# Apollo_2.net
KiCad netlist of a schematic drawn in Altium Designer
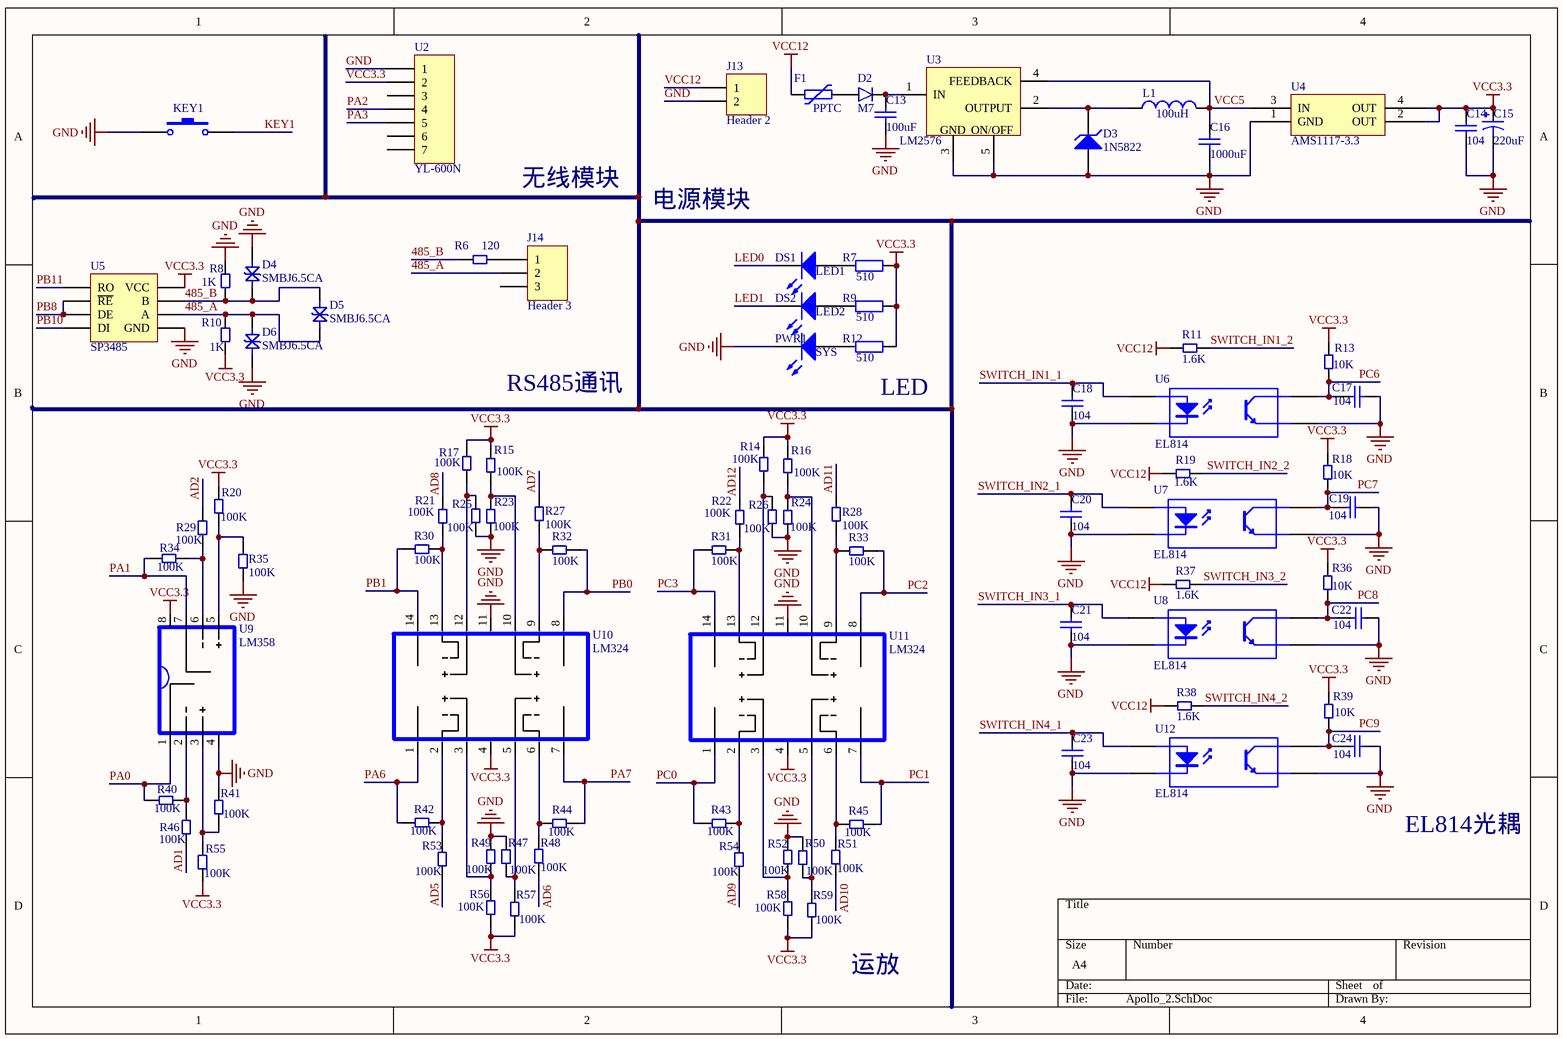
[diagram p0: Apollo_2.SchDoc]

(export (version "E")
  (design (tool "Eeschema 10.0.6"))
  (components
    (comp (ref "C13")
      (value "100uF")
      (footprint "cap3.3-8 - duplicate")
      (description "Capacitor")
      (fields (field (name "PUBLISHER") "Altium Limited"))
      (libsource (lib "Miscellaneous Devices") (part "Cap"))
    )
    (comp (ref "C14")
      (value "104")
      (footprint "0805")
      (description "Capacitor")
      (fields (field (name "Comment") "Cap") (field (name "PUBLISHER") "Altium Limited"))
      (libsource (lib "Miscellaneous Devices") (part "Cap"))
    )
    (comp (ref "C15")
      (value "220uF")
      (footprint "Apollo:C15")
      (description "Polarized Capacitor (Radial)")
      (fields (field (name "Comment") "Cap Pol1") (field (name "PUBLISHER") "Altium Limited"))
      (libsource (lib "Miscellaneous Devices") (part "Cap Pol1"))
    )
    (comp (ref "C16")
      (value "1000uF")
      (footprint "C16")
      (description "Capacitor")
      (fields (field (name "PUBLISHER") "Altium Limited"))
      (libsource (lib "Miscellaneous Devices") (part "Cap"))
    )
    (comp (ref "C17")
      (value "104")
      (footprint "0805C")
      (description "Capacitor")
      (fields (field (name "PUBLISHER") "Altium Limited"))
      (libsource (lib "Miscellaneous Devices") (part "Cap"))
    )
    (comp (ref "C18")
      (value "104")
      (footprint "0805C")
      (description "Capacitor")
      (fields (field (name "PUBLISHER") "Altium Limited"))
      (libsource (lib "Miscellaneous Devices") (part "Cap"))
    )
    (comp (ref "C19")
      (value "104")
      (footprint "0805C")
      (description "Capacitor")
      (fields (field (name "PUBLISHER") "Altium Limited"))
      (libsource (lib "Miscellaneous Devices") (part "Cap"))
    )
    (comp (ref "C20")
      (value "104")
      (footprint "0805C")
      (description "Capacitor")
      (fields (field (name "PUBLISHER") "Altium Limited"))
      (libsource (lib "Miscellaneous Devices") (part "Cap"))
    )
    (comp (ref "C21")
      (value "104")
      (footprint "0805C")
      (description "Capacitor")
      (fields (field (name "PUBLISHER") "Altium Limited"))
      (libsource (lib "Miscellaneous Devices") (part "Cap"))
    )
    (comp (ref "C22")
      (value "104")
      (footprint "0805C")
      (description "Capacitor")
      (fields (field (name "PUBLISHER") "Altium Limited"))
      (libsource (lib "Miscellaneous Devices") (part "Cap"))
    )
    (comp (ref "C23")
      (value "104")
      (footprint "0805C")
      (description "Capacitor")
      (fields (field (name "PUBLISHER") "Altium Limited"))
      (libsource (lib "Miscellaneous Devices") (part "Cap"))
    )
    (comp (ref "C24")
      (value "104")
      (footprint "0805C")
      (description "Capacitor")
      (fields (field (name "PUBLISHER") "Altium Limited"))
      (libsource (lib "Miscellaneous Devices") (part "Cap"))
    )
    (comp (ref "D2") (value "M7") (footprint "SMA (DO-214AC)") (libsource (lib "基本元件") (part "M7")))
    (comp (ref "D3")
      (value "1N5822")
      (footprint "smb do214aa")
      (description "Zener Diode")
      (fields (field (name "PUBLISHER") "Altium Limited"))
      (libsource (lib "Miscellaneous Devices") (part "D Zener"))
    )
    (comp (ref "D4") (value "SMBJ6.5CA") (footprint "smb do214aa") (libsource (lib "基本") (part "SMBJ6.5CA")))
    (comp (ref "D5") (value "SMBJ6.5CA") (footprint "smb do214aa") (libsource (lib "基本") (part "SMBJ6.5CA")))
    (comp (ref "D6") (value "SMBJ6.5CA") (footprint "smb do214aa") (libsource (lib "基本") (part "SMBJ6.5CA")))
    (comp (ref "DS1")
      (value "LED1")
      (footprint "0805-D")
      (description "Typical INFRARED GaAs LED")
      (fields (field (name "PUBLISHER") "Altium Limited"))
      (libsource (lib "Miscellaneous Devices") (part "LED0"))
    )
    (comp (ref "DS2")
      (value "LED2")
      (footprint "0805-D")
      (description "Typical INFRARED GaAs LED")
      (fields (field (name "PUBLISHER") "Altium Limited"))
      (libsource (lib "Miscellaneous Devices") (part "LED0"))
    )
    (comp (ref "F1") (value "PPTC") (footprint "1206") (libsource (lib "基本") (part "PPTC")))
    (comp (ref "J13")
      (value "Header 2")
      (footprint "2EDG 2-3.80")
      (description "Header, 2-Pin")
      (fields (field (name "PUBLISHER") "Altium Limited"))
      (libsource (lib "Miscellaneous Connectors") (part "Header 2"))
    )
    (comp (ref "J14")
      (value "Header 3")
      (footprint "HDR1X3")
      (description "Header, 3-Pin")
      (fields (field (name "PUBLISHER") "Altium Limited"))
      (libsource (lib "Miscellaneous Connectors") (part "Header 3"))
    )
    (comp (ref "KEY1")
      (value "SW-PB")
      (footprint "SWITCH")
      (description "Switch")
      (fields (field (name "PUBLISHER") "Altium Limited"))
      (libsource (lib "Miscellaneous Devices") (part "SW-PB"))
    )
    (comp (ref "L1")
      (value "100uH")
      (footprint "l1212")
      (description "Inductor")
      (fields (field (name "PUBLISHER") "Altium Limited"))
      (libsource (lib "Miscellaneous Devices") (part "Inductor"))
    )
    (comp (ref "PWR1")
      (value "SYS")
      (footprint "0805-D")
      (description "Typical INFRARED GaAs LED")
      (fields (field (name "PUBLISHER") "Altium Limited"))
      (libsource (lib "Miscellaneous Devices") (part "LED0"))
    )
    (comp (ref "R6") (value "120") (footprint "0805") (libsource (lib "基本") (part "Res")))
    (comp (ref "R7")
      (value "510")
      (footprint "0805")
      (description "Resistor")
      (fields (field (name "PUBLISHER") "Altium Limited"))
      (libsource (lib "Miscellaneous Devices") (part "Res2"))
    )
    (comp (ref "R8") (value "1K") (footprint "0805") (libsource (lib "基本") (part "Res")))
    (comp (ref "R9")
      (value "510")
      (footprint "0805")
      (description "Resistor")
      (fields (field (name "PUBLISHER") "Altium Limited"))
      (libsource (lib "Miscellaneous Devices") (part "Res2"))
    )
    (comp (ref "R10") (value "1K") (footprint "0805") (libsource (lib "基本") (part "Res")))
    (comp (ref "R11") (value "1.6K") (footprint "0805") (libsource (lib "基本") (part "Res")))
    (comp (ref "R12")
      (value "510")
      (footprint "0805")
      (description "Resistor")
      (fields (field (name "PUBLISHER") "Altium Limited"))
      (libsource (lib "Miscellaneous Devices") (part "Res2"))
    )
    (comp (ref "R13") (value "10K") (footprint "0805") (libsource (lib "基本") (part "Res")))
    (comp (ref "R14") (value "100K") (footprint "0805") (libsource (lib "基本") (part "Res")))
    (comp (ref "R15") (value "100K") (footprint "0805") (libsource (lib "基本") (part "Res")))
    (comp (ref "R16") (value "100K") (footprint "0805") (libsource (lib "基本") (part "Res")))
    (comp (ref "R17") (value "100K") (footprint "0805") (libsource (lib "基本") (part "Res")))
    (comp (ref "R18") (value "10K") (footprint "0805") (libsource (lib "基本") (part "Res")))
    (comp (ref "R19") (value "1.6K") (footprint "0805") (libsource (lib "基本") (part "Res")))
    (comp (ref "R20") (value "100K") (footprint "0805") (libsource (lib "基本") (part "Res")))
    (comp (ref "R21") (value "100K") (footprint "0805") (libsource (lib "基本") (part "Res")))
    (comp (ref "R22") (value "100K") (footprint "0805") (libsource (lib "基本") (part "Res")))
    (comp (ref "R23") (value "100K") (footprint "0805") (libsource (lib "基本") (part "Res")))
    (comp (ref "R24") (value "100K") (footprint "0805") (libsource (lib "基本") (part "Res")))
    (comp (ref "R25") (value "100K") (footprint "0805") (libsource (lib "基本") (part "Res")))
    (comp (ref "R26") (value "100K") (footprint "0805") (libsource (lib "基本") (part "Res")))
    (comp (ref "R27") (value "100K") (footprint "0805") (libsource (lib "基本") (part "Res")))
    (comp (ref "R28") (value "100K") (footprint "0805") (libsource (lib "基本") (part "Res")))
    (comp (ref "R29") (value "100K") (footprint "0805") (libsource (lib "基本") (part "Res")))
    (comp (ref "R30") (value "100K") (footprint "0805") (libsource (lib "基本") (part "Res")))
    (comp (ref "R31") (value "100K") (footprint "0805") (libsource (lib "基本") (part "Res")))
    (comp (ref "R32") (value "100K") (footprint "0805") (libsource (lib "基本") (part "Res")))
    (comp (ref "R33") (value "100K") (footprint "0805") (libsource (lib "基本") (part "Res")))
    (comp (ref "R34") (value "100K") (footprint "0805") (libsource (lib "基本") (part "Res")))
    (comp (ref "R35") (value "100K") (footprint "0805") (libsource (lib "基本") (part "Res")))
    (comp (ref "R36") (value "10K") (footprint "0805") (libsource (lib "基本") (part "Res")))
    (comp (ref "R37") (value "1.6K") (footprint "0805") (libsource (lib "基本") (part "Res")))
    (comp (ref "R38") (value "1.6K") (footprint "0805") (libsource (lib "基本") (part "Res")))
    (comp (ref "R39") (value "10K") (footprint "0805") (libsource (lib "基本") (part "Res")))
    (comp (ref "R40") (value "100K") (footprint "0805") (libsource (lib "基本") (part "Res")))
    (comp (ref "R41") (value "100K") (footprint "0805") (libsource (lib "基本") (part "Res")))
    (comp (ref "R42") (value "100K") (footprint "0805") (libsource (lib "基本") (part "Res")))
    (comp (ref "R43") (value "100K") (footprint "0805") (libsource (lib "基本") (part "Res")))
    (comp (ref "R44") (value "100K") (footprint "0805") (libsource (lib "基本") (part "Res")))
    (comp (ref "R45") (value "100K") (footprint "0805") (libsource (lib "基本") (part "Res")))
    (comp (ref "R46") (value "100K") (footprint "0805") (libsource (lib "基本") (part "Res")))
    (comp (ref "R47") (value "100K") (footprint "0805") (libsource (lib "基本") (part "Res")))
    (comp (ref "R48") (value "100K") (footprint "0805") (libsource (lib "基本") (part "Res")))
    (comp (ref "R49") (value "100K") (footprint "0805") (libsource (lib "基本") (part "Res")))
    (comp (ref "R50") (value "100K") (footprint "0805") (libsource (lib "基本") (part "Res")))
    (comp (ref "R51") (value "100K") (footprint "0805") (libsource (lib "基本") (part "Res")))
    (comp (ref "R52") (value "100K") (footprint "0805") (libsource (lib "基本") (part "Res")))
    (comp (ref "R53") (value "100K") (footprint "0805") (libsource (lib "基本") (part "Res")))
    (comp (ref "R54") (value "100K") (footprint "0805") (libsource (lib "基本") (part "Res")))
    (comp (ref "R55") (value "100K") (footprint "0805") (libsource (lib "基本") (part "Res")))
    (comp (ref "R56") (value "100K") (footprint "0805") (libsource (lib "基本") (part "Res")))
    (comp (ref "R57") (value "100K") (footprint "0805") (libsource (lib "基本") (part "Res")))
    (comp (ref "R58") (value "100K") (footprint "0805") (libsource (lib "基本") (part "Res")))
    (comp (ref "R59") (value "100K") (footprint "0805") (libsource (lib "基本") (part "Res")))
    (comp (ref "U2")
      (value "YL-600N")
      (footprint "HDR1X7")
      (description "Header, 7-Pin")
      (fields (field (name "PUBLISHER") "Altium Limited"))
      (libsource (lib "Miscellaneous Connectors") (part "Header 7"))
    )
    (comp (ref "U3") (value "LM2576") (footprint "TO-263-5") (libsource (lib "STM32") (part "LM2576")))
    (comp (ref "U4")
      (value "AMS1117-3.3")
      (footprint "AMS1117-3.3")
      (libsource (lib "AMS1117-3.3") (part "AMS1117-3.3"))
    )
    (comp (ref "U5") (value "SP3485") (footprint "sop8") (libsource (lib "常用数字芯片") (part "SP3485")))
    (comp (ref "U6") (value "EL814") (footprint "SOP4") (libsource (lib "*") (part "TLP281")))
    (comp (ref "U7") (value "EL814") (footprint "SOP4") (libsource (lib "*") (part "TLP281")))
    (comp (ref "U8") (value "EL814") (footprint "SOP4") (libsource (lib "*") (part "TLP281")))
    (comp (ref "U9") (value "LM358") (footprint "sop8") (libsource (lib "Apollo") (part "LM358")))
    (comp (ref "U10") (value "LM324") (footprint "SOP-14") (libsource (lib "STM32") (part "LM324N")))
    (comp (ref "U11") (value "LM324") (footprint "SOP-14") (libsource (lib "STM32") (part "LM324N")))
    (comp (ref "U12") (value "EL814") (footprint "SOP4") (libsource (lib "*") (part "TLP281")))
  )
  (nets
    (net (code "1") (name "/485_A") (class "Default")
      (node (ref "D5") (pin "2") (pinfunction "2_2") (pintype "passive"))
      (node (ref "D6") (pin "1") (pinfunction "1_1") (pintype "passive"))
      (node (ref "J14") (pin "2") (pinfunction "2_2") (pintype "passive"))
      (node (ref "R10") (pin "2") (pinfunction "2_2") (pintype "passive"))
      (node (ref "U5") (pin "6") (pinfunction "A_6") (pintype "passive"))
    )
    (net (code "2") (name "/485_B") (class "Default")
      (node (ref "D4") (pin "2") (pinfunction "2_2") (pintype "passive"))
      (node (ref "D5") (pin "1") (pinfunction "1_1") (pintype "passive"))
      (node (ref "R6") (pin "2") (pinfunction "2_2") (pintype "passive"))
      (node (ref "R8") (pin "1") (pinfunction "1_1") (pintype "passive"))
      (node (ref "U5") (pin "7") (pinfunction "B_7") (pintype "passive"))
    )
    (net (code "3") (name "/AD1") (class "Default")
      (node (ref "R46") (pin "1") (pinfunction "1_1") (pintype "passive"))
    )
    (net (code "4") (name "/AD2") (class "Default")
      (node (ref "R29") (pin "2") (pinfunction "2_2") (pintype "passive"))
    )
    (net (code "5") (name "/AD5") (class "Default")
      (node (ref "R53") (pin "1") (pinfunction "1_1") (pintype "passive"))
    )
    (net (code "6") (name "/AD6") (class "Default")
      (node (ref "R48") (pin "1") (pinfunction "1_1") (pintype "passive"))
    )
    (net (code "7") (name "/AD7") (class "Default")
      (node (ref "R27") (pin "1") (pinfunction "1_1") (pintype "passive"))
    )
    (net (code "8") (name "/AD8") (class "Default")
      (node (ref "R21") (pin "1") (pinfunction "1_1") (pintype "passive"))
    )
    (net (code "9") (name "/AD9") (class "Default")
      (node (ref "R54") (pin "1") (pinfunction "1_1") (pintype "passive"))
    )
    (net (code "10") (name "/AD10") (class "Default")
      (node (ref "R51") (pin "1") (pinfunction "1_1") (pintype "passive"))
    )
    (net (code "11") (name "/AD11") (class "Default")
      (node (ref "R28") (pin "1") (pinfunction "1_1") (pintype "passive"))
    )
    (net (code "12") (name "/AD12") (class "Default")
      (node (ref "R22") (pin "1") (pinfunction "1_1") (pintype "passive"))
    )
    (net (code "14") (name "/KEY1") (class "Default")
      (node (ref "KEY1") (pin "2") (pinfunction "2_2") (pintype "passive"))
    )
    (net (code "16") (name "/LED0") (class "Default")
      (node (ref "DS1") (pin "2") (pinfunction "K_2") (pintype "passive"))
    )
    (net (code "17") (name "/LED1") (class "Default")
      (node (ref "DS2") (pin "2") (pinfunction "K_2") (pintype "passive"))
    )
    (net (code "18") (name "/PA0") (class "Default")
      (node (ref "R40") (pin "2") (pinfunction "2_2") (pintype "passive"))
      (node (ref "U9") (pin "1") (pintype "passive"))
    )
    (net (code "19") (name "/PA1") (class "Default")
      (node (ref "R34") (pin "2") (pinfunction "2_2") (pintype "passive"))
      (node (ref "U9") (pin "7") (pintype "passive"))
    )
    (net (code "20") (name "/PA2") (class "Default")
      (node (ref "U2") (pin "4") (pinfunction "4_4") (pintype "passive"))
    )
    (net (code "21") (name "/PA3") (class "Default")
      (node (ref "U2") (pin "5") (pinfunction "5_5") (pintype "passive"))
    )
    (net (code "22") (name "/PA6") (class "Default")
      (node (ref "R42") (pin "2") (pinfunction "2_2") (pintype "passive"))
      (node (ref "U10") (pin "1") (pintype "passive"))
    )
    (net (code "23") (name "/PA7") (class "Default")
      (node (ref "R44") (pin "1") (pinfunction "1_1") (pintype "passive"))
      (node (ref "U10") (pin "7") (pintype "passive"))
    )
    (net (code "24") (name "/PB0") (class "Default")
      (node (ref "R32") (pin "2") (pinfunction "2_2") (pintype "passive"))
      (node (ref "U10") (pin "8") (pintype "passive"))
    )
    (net (code "25") (name "/PB1") (class "Default")
      (node (ref "R30") (pin "1") (pinfunction "1_1") (pintype "passive"))
      (node (ref "U10") (pin "14") (pintype "passive"))
    )
    (net (code "26") (name "/PB8") (class "Default")
      (node (ref "U5") (pin "2") (pinfunction "~{RE}_2") (pintype "passive"))
      (node (ref "U5") (pin "3") (pinfunction "DE_3") (pintype "passive"))
    )
    (net (code "27") (name "/PB10") (class "Default")
      (node (ref "U5") (pin "4") (pinfunction "DI_4") (pintype "passive"))
    )
    (net (code "28") (name "/PB11") (class "Default")
      (node (ref "U5") (pin "1") (pinfunction "RO_1") (pintype "passive"))
    )
    (net (code "29") (name "/PC0") (class "Default")
      (node (ref "R43") (pin "2") (pinfunction "2_2") (pintype "passive"))
      (node (ref "U11") (pin "1") (pintype "passive"))
    )
    (net (code "30") (name "/PC1") (class "Default")
      (node (ref "R45") (pin "1") (pinfunction "1_1") (pintype "passive"))
      (node (ref "U11") (pin "7") (pintype "passive"))
    )
    (net (code "31") (name "/PC2") (class "Default")
      (node (ref "R33") (pin "2") (pinfunction "2_2") (pintype "passive"))
      (node (ref "U11") (pin "8") (pintype "passive"))
    )
    (net (code "32") (name "/PC3") (class "Default")
      (node (ref "R31") (pin "1") (pinfunction "1_1") (pintype "passive"))
      (node (ref "U11") (pin "14") (pintype "passive"))
    )
    (net (code "33") (name "/PC6") (class "Default")
      (node (ref "C17") (pin "2") (pinfunction "2_2") (pintype "passive"))
      (node (ref "R13") (pin "2") (pinfunction "2_2") (pintype "passive"))
      (node (ref "U6") (pin "4") (pinfunction "C_4") (pintype "passive"))
    )
    (net (code "34") (name "/PC7") (class "Default")
      (node (ref "C19") (pin "2") (pinfunction "2_2") (pintype "passive"))
      (node (ref "R18") (pin "2") (pinfunction "2_2") (pintype "passive"))
      (node (ref "U7") (pin "4") (pinfunction "C_4") (pintype "passive"))
    )
    (net (code "35") (name "/PC8") (class "Default")
      (node (ref "C22") (pin "2") (pinfunction "2_2") (pintype "passive"))
      (node (ref "R36") (pin "2") (pinfunction "2_2") (pintype "passive"))
      (node (ref "U8") (pin "4") (pinfunction "C_4") (pintype "passive"))
    )
    (net (code "36") (name "/PC9") (class "Default")
      (node (ref "C24") (pin "2") (pinfunction "2_2") (pintype "passive"))
      (node (ref "R39") (pin "2") (pinfunction "2_2") (pintype "passive"))
      (node (ref "U12") (pin "4") (pinfunction "C_4") (pintype "passive"))
    )
    (net (code "38") (name "/SWITCH_IN1_1") (class "Default")
      (node (ref "C18") (pin "2") (pinfunction "2_2") (pintype "passive"))
      (node (ref "U6") (pin "1") (pinfunction "A_1") (pintype "passive"))
    )
    (net (code "39") (name "/SWITCH_IN1_2") (class "Default")
      (node (ref "R11") (pin "2") (pinfunction "2_2") (pintype "passive"))
    )
    (net (code "40") (name "/SWITCH_IN2_1") (class "Default")
      (node (ref "C20") (pin "2") (pinfunction "2_2") (pintype "passive"))
      (node (ref "U7") (pin "1") (pinfunction "A_1") (pintype "passive"))
    )
    (net (code "41") (name "/SWITCH_IN2_2") (class "Default")
      (node (ref "R19") (pin "2") (pinfunction "2_2") (pintype "passive"))
    )
    (net (code "42") (name "/SWITCH_IN3_1") (class "Default")
      (node (ref "C21") (pin "2") (pinfunction "2_2") (pintype "passive"))
      (node (ref "U8") (pin "1") (pinfunction "A_1") (pintype "passive"))
    )
    (net (code "43") (name "/SWITCH_IN3_2") (class "Default")
      (node (ref "R37") (pin "2") (pinfunction "2_2") (pintype "passive"))
    )
    (net (code "44") (name "/SWITCH_IN4_1") (class "Default")
      (node (ref "C23") (pin "2") (pinfunction "2_2") (pintype "passive"))
      (node (ref "U12") (pin "1") (pinfunction "A_1") (pintype "passive"))
    )
    (net (code "45") (name "/SWITCH_IN4_2") (class "Default")
      (node (ref "R38") (pin "2") (pinfunction "2_2") (pintype "passive"))
    )
    (net (code "46") (name "/VCC5") (class "Default")
      (node (ref "C16") (pin "2") (pinfunction "2_2") (pintype "passive"))
      (node (ref "L1") (pin "2") (pinfunction "2_2") (pintype "passive"))
      (node (ref "U3") (pin "4") (pinfunction "FEEDBACK_4") (pintype "passive"))
      (node (ref "U4") (pin "3") (pinfunction "IN_3") (pintype "passive"))
    )
    (net (code "50") (name "GND") (class "Default")
      (node (ref "C13") (pin "1") (pinfunction "1_1") (pintype "passive"))
      (node (ref "C14") (pin "1") (pinfunction "1_1") (pintype "passive"))
      (node (ref "C15") (pin "2") (pinfunction "2_2") (pintype "passive"))
      (node (ref "C16") (pin "1") (pinfunction "1_1") (pintype "passive"))
      (node (ref "C17") (pin "1") (pinfunction "1_1") (pintype "passive"))
      (node (ref "C18") (pin "1") (pinfunction "1_1") (pintype "passive"))
      (node (ref "C19") (pin "1") (pinfunction "1_1") (pintype "passive"))
      (node (ref "C20") (pin "1") (pinfunction "1_1") (pintype "passive"))
      (node (ref "C21") (pin "1") (pinfunction "1_1") (pintype "passive"))
      (node (ref "C22") (pin "1") (pinfunction "1_1") (pintype "passive"))
      (node (ref "C23") (pin "1") (pinfunction "1_1") (pintype "passive"))
      (node (ref "C24") (pin "1") (pinfunction "1_1") (pintype "passive"))
      (node (ref "D3") (pin "1") (pinfunction "A_1") (pintype "passive"))
      (node (ref "D4") (pin "1") (pinfunction "1_1") (pintype "passive"))
      (node (ref "D6") (pin "2") (pinfunction "2_2") (pintype "passive"))
      (node (ref "J13") (pin "2") (pinfunction "2_2") (pintype "passive"))
      (node (ref "KEY1") (pin "1") (pinfunction "1_1") (pintype "passive"))
      (node (ref "PWR1") (pin "2") (pinfunction "K_2") (pintype "passive"))
      (node (ref "R23") (pin "2") (pinfunction "2_2") (pintype "passive"))
      (node (ref "R24") (pin "2") (pinfunction "2_2") (pintype "passive"))
      (node (ref "R25") (pin "2") (pinfunction "2_2") (pintype "passive"))
      (node (ref "R26") (pin "2") (pinfunction "2_2") (pintype "passive"))
      (node (ref "R35") (pin "2") (pinfunction "2_2") (pintype "passive"))
      (node (ref "R41") (pin "2") (pinfunction "2_2") (pintype "passive"))
      (node (ref "R47") (pin "2") (pinfunction "2_2") (pintype "passive"))
      (node (ref "R49") (pin "2") (pinfunction "2_2") (pintype "passive"))
      (node (ref "R50") (pin "2") (pinfunction "2_2") (pintype "passive"))
      (node (ref "R52") (pin "2") (pinfunction "2_2") (pintype "passive"))
      (node (ref "R8") (pin "2") (pinfunction "2_2") (pintype "passive"))
      (node (ref "U10") (pin "11") (pintype "passive"))
      (node (ref "U11") (pin "11") (pintype "passive"))
      (node (ref "U12") (pin "2") (pinfunction "K_2") (pintype "passive"))
      (node (ref "U12") (pin "3") (pinfunction "E_3") (pintype "passive"))
      (node (ref "U2") (pin "1") (pinfunction "1_1") (pintype "passive"))
      (node (ref "U3") (pin "3") (pintype "passive"))
      (node (ref "U3") (pin "5") (pintype "passive"))
      (node (ref "U4") (pin "1") (pinfunction "GND_1") (pintype "passive"))
      (node (ref "U5") (pin "5") (pinfunction "GND_5") (pintype "passive"))
      (node (ref "U6") (pin "2") (pinfunction "K_2") (pintype "passive"))
      (node (ref "U6") (pin "3") (pinfunction "E_3") (pintype "passive"))
      (node (ref "U7") (pin "2") (pinfunction "K_2") (pintype "passive"))
      (node (ref "U7") (pin "3") (pinfunction "E_3") (pintype "passive"))
      (node (ref "U8") (pin "2") (pinfunction "K_2") (pintype "passive"))
      (node (ref "U8") (pin "3") (pinfunction "E_3") (pintype "passive"))
      (node (ref "U9") (pin "4") (pintype "passive"))
    )
    (net (code "51") (name "Net-(D2-+)") (class "Default")
      (node (ref "D2") (pin "2") (pinfunction "+_2") (pintype "passive"))
      (node (ref "F1") (pin "2") (pinfunction "2_2") (pintype "passive"))
    )
    (net (code "52") (name "Net-(D2--)") (class "Default")
      (node (ref "C13") (pin "2") (pinfunction "2_2") (pintype "passive"))
      (node (ref "D2") (pin "1") (pinfunction "-_1") (pintype "passive"))
      (node (ref "U3") (pin "1") (pinfunction "IN_1") (pintype "passive"))
    )
    (net (code "53") (name "Net-(D3-K)") (class "Default")
      (node (ref "D3") (pin "2") (pinfunction "K_2") (pintype "passive"))
      (node (ref "L1") (pin "1") (pinfunction "1_1") (pintype "passive"))
      (node (ref "U3") (pin "2") (pinfunction "OUTPUT_2") (pintype "passive"))
    )
    (net (code "54") (name "Net-(DS1-A)") (class "Default")
      (node (ref "DS1") (pin "1") (pinfunction "A_1") (pintype "passive"))
      (node (ref "R7") (pin "1") (pinfunction "1_1") (pintype "passive"))
    )
    (net (code "55") (name "Net-(DS2-A)") (class "Default")
      (node (ref "DS2") (pin "1") (pinfunction "A_1") (pintype "passive"))
      (node (ref "R9") (pin "1") (pinfunction "1_1") (pintype "passive"))
    )
    (net (code "56") (name "Net-(J14-Pad1)") (class "Default")
      (node (ref "J14") (pin "1") (pinfunction "1_1") (pintype "passive"))
      (node (ref "R6") (pin "1") (pinfunction "1_1") (pintype "passive"))
    )
    (net (code "57") (name "Net-(PWR1-A)") (class "Default")
      (node (ref "PWR1") (pin "1") (pinfunction "A_1") (pintype "passive"))
      (node (ref "R12") (pin "1") (pinfunction "1_1") (pintype "passive"))
    )
    (net (code "58") (name "Net-(R14-Pad2)") (class "Default")
      (node (ref "R14") (pin "2") (pinfunction "2_2") (pintype "passive"))
      (node (ref "R26") (pin "1") (pinfunction "1_1") (pintype "passive"))
      (node (ref "U11") (pin "12") (pintype "passive"))
    )
    (net (code "59") (name "Net-(R15-Pad2)") (class "Default")
      (node (ref "R15") (pin "2") (pinfunction "2_2") (pintype "passive"))
      (node (ref "R23") (pin "1") (pinfunction "1_1") (pintype "passive"))
      (node (ref "U10") (pin "10") (pintype "passive"))
    )
    (net (code "60") (name "Net-(R16-Pad2)") (class "Default")
      (node (ref "R16") (pin "2") (pinfunction "2_2") (pintype "passive"))
      (node (ref "R24") (pin "1") (pinfunction "1_1") (pintype "passive"))
      (node (ref "U11") (pin "10") (pintype "passive"))
    )
    (net (code "61") (name "Net-(R17-Pad2)") (class "Default")
      (node (ref "R17") (pin "2") (pinfunction "2_2") (pintype "passive"))
      (node (ref "R25") (pin "1") (pinfunction "1_1") (pintype "passive"))
      (node (ref "U10") (pin "12") (pintype "passive"))
    )
    (net (code "62") (name "Net-(R20-Pad1)") (class "Default")
      (node (ref "R20") (pin "1") (pinfunction "1_1") (pintype "passive"))
      (node (ref "R35") (pin "1") (pinfunction "1_1") (pintype "passive"))
      (node (ref "U9") (pin "5") (pintype "passive"))
    )
    (net (code "63") (name "Net-(R21-Pad2)") (class "Default")
      (node (ref "R21") (pin "2") (pinfunction "2_2") (pintype "passive"))
      (node (ref "R30") (pin "2") (pinfunction "2_2") (pintype "passive"))
      (node (ref "U10") (pin "13") (pintype "passive"))
    )
    (net (code "64") (name "Net-(R22-Pad2)") (class "Default")
      (node (ref "R22") (pin "2") (pinfunction "2_2") (pintype "passive"))
      (node (ref "R31") (pin "2") (pinfunction "2_2") (pintype "passive"))
      (node (ref "U11") (pin "13") (pintype "passive"))
    )
    (net (code "65") (name "Net-(R27-Pad2)") (class "Default")
      (node (ref "R27") (pin "2") (pinfunction "2_2") (pintype "passive"))
      (node (ref "R32") (pin "1") (pinfunction "1_1") (pintype "passive"))
      (node (ref "U10") (pin "9") (pintype "passive"))
    )
    (net (code "66") (name "Net-(R28-Pad2)") (class "Default")
      (node (ref "R28") (pin "2") (pinfunction "2_2") (pintype "passive"))
      (node (ref "R33") (pin "1") (pinfunction "1_1") (pintype "passive"))
      (node (ref "U11") (pin "9") (pintype "passive"))
    )
    (net (code "67") (name "Net-(R29-Pad1)") (class "Default")
      (node (ref "R29") (pin "1") (pinfunction "1_1") (pintype "passive"))
      (node (ref "R34") (pin "1") (pinfunction "1_1") (pintype "passive"))
      (node (ref "U9") (pin "6") (pintype "passive"))
    )
    (net (code "68") (name "Net-(R40-Pad1)") (class "Default")
      (node (ref "R40") (pin "1") (pinfunction "1_1") (pintype "passive"))
      (node (ref "R46") (pin "2") (pinfunction "2_2") (pintype "passive"))
      (node (ref "U9") (pin "2") (pintype "passive"))
    )
    (net (code "69") (name "Net-(R41-Pad1)") (class "Default")
      (node (ref "R41") (pin "1") (pinfunction "1_1") (pintype "passive"))
      (node (ref "R55") (pin "2") (pinfunction "2_2") (pintype "passive"))
      (node (ref "U9") (pin "3") (pintype "passive"))
    )
    (net (code "70") (name "Net-(R42-Pad1)") (class "Default")
      (node (ref "R42") (pin "1") (pinfunction "1_1") (pintype "passive"))
      (node (ref "R53") (pin "2") (pinfunction "2_2") (pintype "passive"))
      (node (ref "U10") (pin "2") (pintype "passive"))
    )
    (net (code "71") (name "Net-(R43-Pad1)") (class "Default")
      (node (ref "R43") (pin "1") (pinfunction "1_1") (pintype "passive"))
      (node (ref "R54") (pin "2") (pinfunction "2_2") (pintype "passive"))
      (node (ref "U11") (pin "2") (pintype "passive"))
    )
    (net (code "72") (name "Net-(R44-Pad2)") (class "Default")
      (node (ref "R44") (pin "2") (pinfunction "2_2") (pintype "passive"))
      (node (ref "R48") (pin "2") (pinfunction "2_2") (pintype "passive"))
      (node (ref "U10") (pin "6") (pintype "passive"))
    )
    (net (code "73") (name "Net-(R45-Pad2)") (class "Default")
      (node (ref "R45") (pin "2") (pinfunction "2_2") (pintype "passive"))
      (node (ref "R51") (pin "2") (pinfunction "2_2") (pintype "passive"))
      (node (ref "U11") (pin "6") (pintype "passive"))
    )
    (net (code "74") (name "Net-(R47-Pad1)") (class "Default")
      (node (ref "R47") (pin "1") (pinfunction "1_1") (pintype "passive"))
      (node (ref "R57") (pin "2") (pinfunction "2_2") (pintype "passive"))
      (node (ref "U10") (pin "5") (pintype "passive"))
    )
    (net (code "75") (name "Net-(R49-Pad1)") (class "Default")
      (node (ref "R49") (pin "1") (pinfunction "1_1") (pintype "passive"))
      (node (ref "R56") (pin "2") (pinfunction "2_2") (pintype "passive"))
      (node (ref "U10") (pin "3") (pintype "passive"))
    )
    (net (code "76") (name "Net-(R50-Pad1)") (class "Default")
      (node (ref "R50") (pin "1") (pinfunction "1_1") (pintype "passive"))
      (node (ref "R59") (pin "2") (pinfunction "2_2") (pintype "passive"))
      (node (ref "U11") (pin "5") (pintype "passive"))
    )
    (net (code "77") (name "Net-(R52-Pad1)") (class "Default")
      (node (ref "R52") (pin "1") (pinfunction "1_1") (pintype "passive"))
      (node (ref "R58") (pin "2") (pinfunction "2_2") (pintype "passive"))
      (node (ref "U11") (pin "3") (pintype "passive"))
    )
    (net (code "78") (name "VCC3.3") (class "Default")
      (node (ref "C14") (pin "2") (pinfunction "2_2") (pintype "passive"))
      (node (ref "C15") (pin "1") (pinfunction "1_1") (pintype "passive"))
      (node (ref "R10") (pin "1") (pinfunction "1_1") (pintype "passive"))
      (node (ref "R12") (pin "2") (pinfunction "2_2") (pintype "passive"))
      (node (ref "R13") (pin "1") (pinfunction "1_1") (pintype "passive"))
      (node (ref "R14") (pin "1") (pinfunction "1_1") (pintype "passive"))
      (node (ref "R15") (pin "1") (pinfunction "1_1") (pintype "passive"))
      (node (ref "R16") (pin "1") (pinfunction "1_1") (pintype "passive"))
      (node (ref "R17") (pin "1") (pinfunction "1_1") (pintype "passive"))
      (node (ref "R18") (pin "1") (pinfunction "1_1") (pintype "passive"))
      (node (ref "R20") (pin "2") (pinfunction "2_2") (pintype "passive"))
      (node (ref "R36") (pin "1") (pinfunction "1_1") (pintype "passive"))
      (node (ref "R39") (pin "1") (pinfunction "1_1") (pintype "passive"))
      (node (ref "R55") (pin "1") (pinfunction "1_1") (pintype "passive"))
      (node (ref "R56") (pin "1") (pinfunction "1_1") (pintype "passive"))
      (node (ref "R57") (pin "1") (pinfunction "1_1") (pintype "passive"))
      (node (ref "R58") (pin "1") (pinfunction "1_1") (pintype "passive"))
      (node (ref "R59") (pin "1") (pinfunction "1_1") (pintype "passive"))
      (node (ref "R7") (pin "2") (pinfunction "2_2") (pintype "passive"))
      (node (ref "R9") (pin "2") (pinfunction "2_2") (pintype "passive"))
      (node (ref "U10") (pin "4") (pintype "passive"))
      (node (ref "U11") (pin "4") (pintype "passive"))
      (node (ref "U2") (pin "2") (pinfunction "2_2") (pintype "passive"))
      (node (ref "U4") (pin "2") (pinfunction "OUT_2") (pintype "passive"))
      (node (ref "U4") (pin "4") (pinfunction "OUT_4") (pintype "passive"))
      (node (ref "U5") (pin "8") (pinfunction "VCC_8") (pintype "passive"))
      (node (ref "U9") (pin "8") (pintype "passive"))
    )
    (net (code "79") (name "VCC12") (class "Default")
      (node (ref "F1") (pin "1") (pinfunction "1_1") (pintype "passive"))
      (node (ref "J13") (pin "1") (pinfunction "1_1") (pintype "passive"))
      (node (ref "R11") (pin "1") (pinfunction "1_1") (pintype "passive"))
      (node (ref "R19") (pin "1") (pinfunction "1_1") (pintype "passive"))
      (node (ref "R37") (pin "1") (pinfunction "1_1") (pintype "passive"))
      (node (ref "R38") (pin "1") (pinfunction "1_1") (pintype "passive"))
    )
    (net (code "80") (name "unconnected-(J14-Pad3)") (class "Default")
      (node (ref "J14") (pin "3") (pinfunction "3_3") (pintype "passive"))
    )
    (net (code "81") (name "unconnected-(U2-Pad3)") (class "Default")
      (node (ref "U2") (pin "3") (pinfunction "3_3") (pintype "passive"))
    )
    (net (code "82") (name "unconnected-(U2-Pad6)") (class "Default")
      (node (ref "U2") (pin "6") (pinfunction "6_6") (pintype "passive"))
    )
    (net (code "83") (name "unconnected-(U2-Pad7)") (class "Default")
      (node (ref "U2") (pin "7") (pinfunction "7_7") (pintype "passive"))
    )
  )
)
